# PiPico_Pinout.net
KiCad netlist of a schematic drawn in Altium Designer
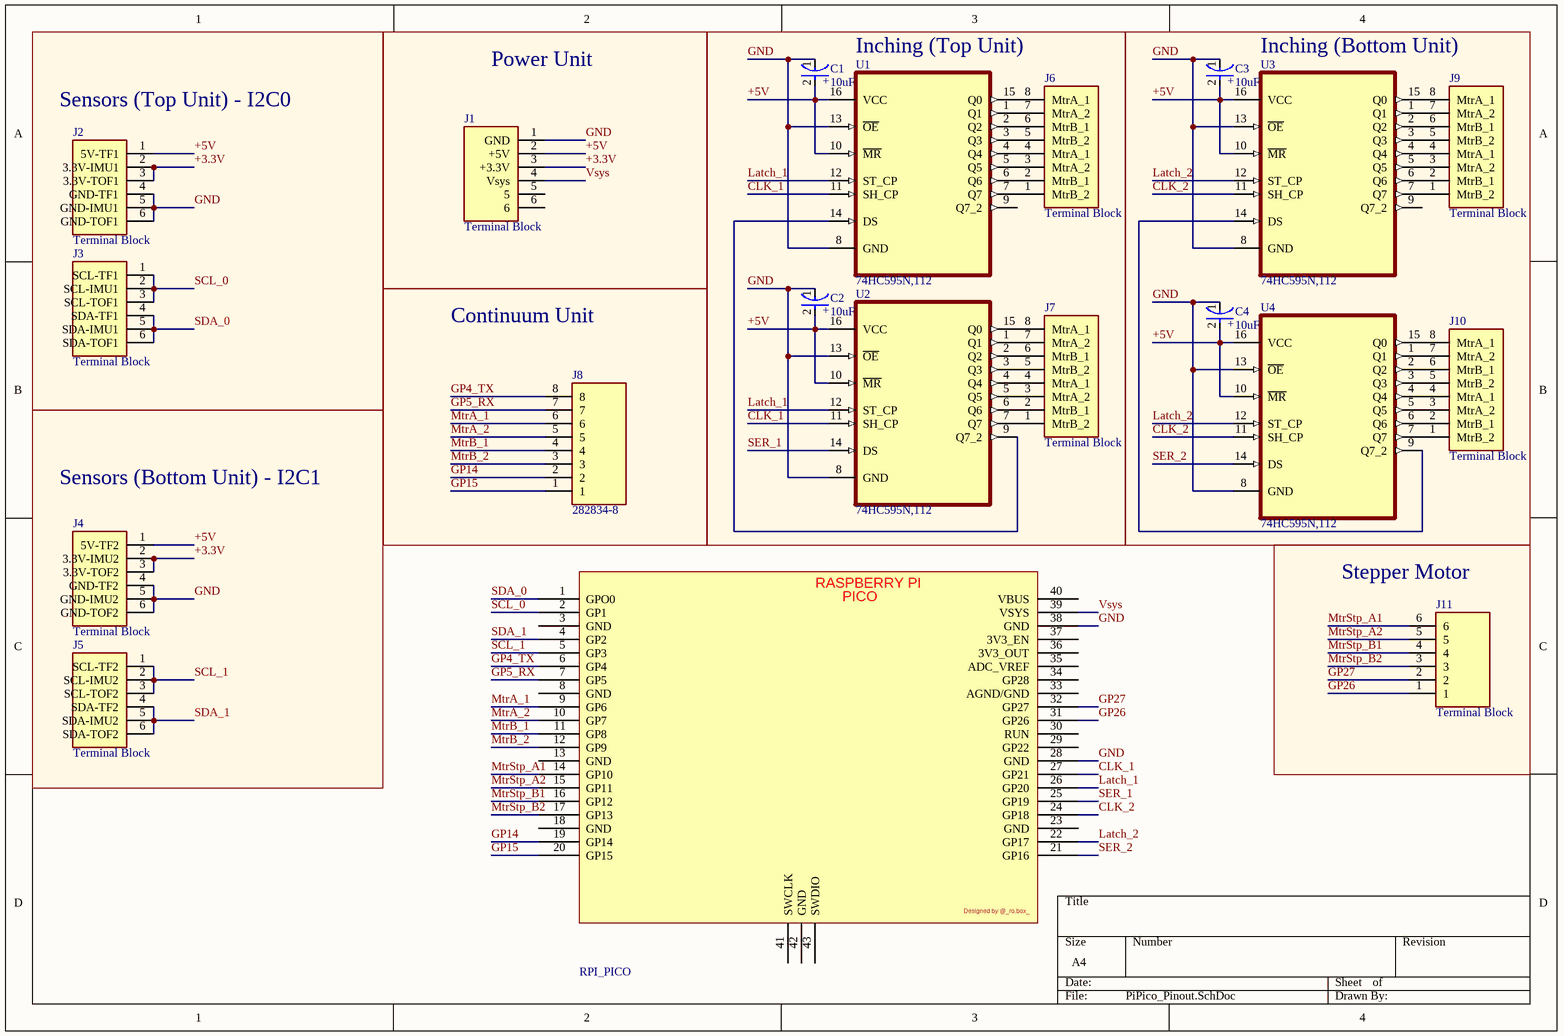
[diagram p0: PiPico_Pinout.SchDoc]

(export (version "E")
  (design (tool "Eeschema 10.0.6"))
  (components
    (comp (ref "C1")
      (value "10uF")
      (footprint "FP-TAP106K016SCS-MFG")
      (description "CAP TANT 10UF 10% 16V RADIAL")
      (fields (field (name "TOLERANCE") "10%") (field (name "VOLTAGE") "16V"))
      (libsource (lib "Altium Content Vault") (part "cf48714ba7e38822c1575c7ec0b6d1f"))
    )
    (comp (ref "C2")
      (value "10uF")
      (footprint "FP-TAP106K016SCS-MFG")
      (description "CAP TANT 10UF 10% 16V RADIAL")
      (fields (field (name "TOLERANCE") "10%") (field (name "VOLTAGE") "16V"))
      (libsource (lib "Altium Content Vault") (part "cf48714ba7e38822c1575c7ec0b6d1f"))
    )
    (comp (ref "C3")
      (value "10uF")
      (footprint "FP-TAP106K016SCS-MFG")
      (description "CAP TANT 10UF 10% 16V RADIAL")
      (fields (field (name "TOLERANCE") "10%") (field (name "VOLTAGE") "16V"))
      (libsource (lib "Altium Content Vault") (part "cf48714ba7e38822c1575c7ec0b6d1f"))
    )
    (comp (ref "C4")
      (value "10uF")
      (footprint "FP-TAP106K016SCS-MFG")
      (description "CAP TANT 10UF 10% 16V RADIAL")
      (fields (field (name "TOLERANCE") "10%") (field (name "VOLTAGE") "16V"))
      (libsource (lib "Altium Content Vault") (part "cf48714ba7e38822c1575c7ec0b6d1f"))
    )
    (comp (ref "J1")
      (value "Terminal Block")
      (footprint "TE_282834-6")
      (fields (field (name "MP") "282834-6") (field (name "MF") "{'manufacturer': 'TE Connectivity'}"))
      (libsource (lib "6pin_ScrewTerminal_2.54mm") (part "282834-6"))
    )
    (comp (ref "J2")
      (value "Terminal Block")
      (footprint "TE_282834-6")
      (fields (field (name "MP") "282834-6") (field (name "MF") "{'manufacturer': 'TE Connectivity'}"))
      (libsource (lib "6pin_ScrewTerminal_2.54mm") (part "282834-6"))
    )
    (comp (ref "J3")
      (value "Terminal Block")
      (footprint "TE_282834-6")
      (fields (field (name "MP") "282834-6") (field (name "MF") "{'manufacturer': 'TE Connectivity'}"))
      (libsource (lib "6pin_ScrewTerminal_2.54mm") (part "282834-6"))
    )
    (comp (ref "J4")
      (value "Terminal Block")
      (footprint "TE_282834-6")
      (fields (field (name "MP") "282834-6") (field (name "MF") "{'manufacturer': 'TE Connectivity'}"))
      (libsource (lib "6pin_ScrewTerminal_2.54mm") (part "282834-6"))
    )
    (comp (ref "J5")
      (value "Terminal Block")
      (footprint "TE_282834-6")
      (fields (field (name "MP") "282834-6") (field (name "MF") "{'manufacturer': 'TE Connectivity'}"))
      (libsource (lib "6pin_ScrewTerminal_2.54mm") (part "282834-6"))
    )
    (comp (ref "J6")
      (value "Terminal Block")
      (footprint "TE_282834-8")
      (description "Buchanan; Conn; Term Blk; PCB; 8; 2.54mm; Front; 30-16 AWG; Green; 10 A; 150 V")
      (fields (field (name "MF") "TE Connectivity") (field (name "DIGI-KEY_PART_NUMBER") "A98338-ND"))
      (libsource (lib "8pin_ScrewTerminal_2.54mm") (part "282834-8"))
    )
    (comp (ref "J7")
      (value "Terminal Block")
      (footprint "TE_282834-8")
      (description "Buchanan; Conn; Term Blk; PCB; 8; 2.54mm; Front; 30-16 AWG; Green; 10 A; 150 V")
      (fields (field (name "MF") "TE Connectivity") (field (name "DIGI-KEY_PART_NUMBER") "A98338-ND"))
      (libsource (lib "8pin_ScrewTerminal_2.54mm") (part "282834-8"))
    )
    (comp (ref "J8")
      (value "282834-8")
      (footprint "TE_282834-8")
      (description "Buchanan; Conn; Term Blk; PCB; 8; 2.54mm; Front; 30-16 AWG; Green; 10 A; 150 V")
      (fields (field (name "MF") "TE Connectivity") (field (name "DIGI-KEY_PART_NUMBER") "A98338-ND"))
      (libsource (lib "8pin_ScrewTerminal_2.54mm") (part "282834-8"))
    )
    (comp (ref "J9")
      (value "Terminal Block")
      (footprint "TE_282834-8")
      (description "Buchanan; Conn; Term Blk; PCB; 8; 2.54mm; Front; 30-16 AWG; Green; 10 A; 150 V")
      (fields (field (name "MF") "TE Connectivity") (field (name "DIGI-KEY_PART_NUMBER") "A98338-ND"))
      (libsource (lib "8pin_ScrewTerminal_2.54mm") (part "282834-8"))
    )
    (comp (ref "J10")
      (value "Terminal Block")
      (footprint "TE_282834-8")
      (description "Buchanan; Conn; Term Blk; PCB; 8; 2.54mm; Front; 30-16 AWG; Green; 10 A; 150 V")
      (fields (field (name "MF") "TE Connectivity") (field (name "DIGI-KEY_PART_NUMBER") "A98338-ND"))
      (libsource (lib "8pin_ScrewTerminal_2.54mm") (part "282834-8"))
    )
    (comp (ref "J11")
      (value "Terminal Block")
      (footprint "TE_282834-6")
      (fields (field (name "MP") "282834-6") (field (name "MF") "{'manufacturer': 'TE Connectivity'}"))
      (libsource (lib "") (part "282834-6_1"))
    )
    (comp (ref "RPI_PICO")
      (value "RPI_PICO")
      (footprint "RPI PICO 2020")
      (libsource (lib "RPI_PICO") (part "RPI_PICO"))
    )
    (comp (ref "U1")
      (value "74HC595N,112")
      (footprint "DIP254P762X420-16")
      (description "Shift Shift Register 1 Element 8 Bit 16-DIP")
      (fields (field (name "MF") "NXP USA"))
      (libsource (lib "74HC595N_112") (part "74HC595N,112"))
    )
    (comp (ref "U2")
      (value "74HC595N,112")
      (footprint "DIP254P762X420-16")
      (description "Shift Shift Register 1 Element 8 Bit 16-DIP")
      (fields (field (name "MF") "NXP USA"))
      (libsource (lib "74HC595N_112") (part "74HC595N,112"))
    )
    (comp (ref "U3")
      (value "74HC595N,112")
      (footprint "DIP254P762X420-16")
      (description "Shift Shift Register 1 Element 8 Bit 16-DIP")
      (fields (field (name "MF") "NXP USA"))
      (libsource (lib "74HC595N_112") (part "74HC595N,112"))
    )
    (comp (ref "U4")
      (value "74HC595N,112")
      (footprint "DIP254P762X420-16")
      (description "Shift Shift Register 1 Element 8 Bit 16-DIP")
      (fields (field (name "MF") "NXP USA"))
      (libsource (lib "74HC595N_112") (part "74HC595N,112"))
    )
  )
  (nets
    (net (code "1") (name "/+3.3V") (class "Default")
      (node (ref "J1") (pin "3") (pinfunction "SCL-TOF2_3") (pintype "passive"))
      (node (ref "J2") (pin "2") (pinfunction "SCL-IMU2_2") (pintype "passive"))
      (node (ref "J2") (pin "3") (pinfunction "SCL-TOF2_3") (pintype "passive"))
      (node (ref "J4") (pin "2") (pinfunction "SCL-IMU2_2") (pintype "passive"))
      (node (ref "J4") (pin "3") (pinfunction "SCL-TOF2_3") (pintype "passive"))
    )
    (net (code "2") (name "/+5V") (class "Default")
      (node (ref "C1") (pin "2") (pinfunction "A_2") (pintype "passive"))
      (node (ref "C2") (pin "2") (pinfunction "A_2") (pintype "passive"))
      (node (ref "C3") (pin "2") (pinfunction "A_2") (pintype "passive"))
      (node (ref "C4") (pin "2") (pinfunction "A_2") (pintype "passive"))
      (node (ref "J1") (pin "2") (pinfunction "SCL-IMU2_2") (pintype "passive"))
      (node (ref "J2") (pin "1") (pinfunction "SCL-TF2_1") (pintype "passive"))
      (node (ref "J4") (pin "1") (pinfunction "SCL-TF2_1") (pintype "passive"))
      (node (ref "U1") (pin "10") (pinfunction "~{MR}_10") (pintype "input"))
      (node (ref "U1") (pin "16") (pinfunction "VCC_16") (pintype "power_in"))
      (node (ref "U2") (pin "10") (pinfunction "~{MR}_10") (pintype "input"))
      (node (ref "U2") (pin "16") (pinfunction "VCC_16") (pintype "power_in"))
      (node (ref "U3") (pin "10") (pinfunction "~{MR}_10") (pintype "input"))
      (node (ref "U3") (pin "16") (pinfunction "VCC_16") (pintype "power_in"))
      (node (ref "U4") (pin "10") (pinfunction "~{MR}_10") (pintype "input"))
      (node (ref "U4") (pin "16") (pinfunction "VCC_16") (pintype "power_in"))
    )
    (net (code "3") (name "/CLK_1") (class "Default")
      (node (ref "RPI_PICO") (pin "27") (pinfunction "GP21_27") (pintype "passive"))
      (node (ref "U1") (pin "11") (pinfunction "SH_CP_11") (pintype "input"))
      (node (ref "U2") (pin "11") (pinfunction "SH_CP_11") (pintype "input"))
    )
    (net (code "4") (name "/CLK_2") (class "Default")
      (node (ref "RPI_PICO") (pin "24") (pinfunction "GP18_24") (pintype "passive"))
      (node (ref "U3") (pin "11") (pinfunction "SH_CP_11") (pintype "input"))
      (node (ref "U4") (pin "11") (pinfunction "SH_CP_11") (pintype "input"))
    )
    (net (code "5") (name "/GND") (class "Default")
      (node (ref "C1") (pin "1") (pinfunction "C_1") (pintype "passive"))
      (node (ref "C2") (pin "1") (pinfunction "C_1") (pintype "passive"))
      (node (ref "C3") (pin "1") (pinfunction "C_1") (pintype "passive"))
      (node (ref "C4") (pin "1") (pinfunction "C_1") (pintype "passive"))
      (node (ref "J1") (pin "1") (pinfunction "SCL-TF2_1") (pintype "passive"))
      (node (ref "J2") (pin "4") (pinfunction "SDA-TF2_4") (pintype "passive"))
      (node (ref "J2") (pin "5") (pinfunction "SDA-IMU2_5") (pintype "passive"))
      (node (ref "J2") (pin "6") (pinfunction "SDA-TOF2_6") (pintype "passive"))
      (node (ref "J4") (pin "4") (pinfunction "SDA-TF2_4") (pintype "passive"))
      (node (ref "J4") (pin "5") (pinfunction "SDA-IMU2_5") (pintype "passive"))
      (node (ref "J4") (pin "6") (pinfunction "SDA-TOF2_6") (pintype "passive"))
      (node (ref "RPI_PICO") (pin "28") (pinfunction "GND_28") (pintype "passive"))
      (node (ref "RPI_PICO") (pin "38") (pinfunction "GND_38") (pintype "passive"))
      (node (ref "U1") (pin "13") (pinfunction "~{OE}_13") (pintype "input"))
      (node (ref "U1") (pin "8") (pinfunction "GND_8") (pintype "passive"))
      (node (ref "U2") (pin "13") (pinfunction "~{OE}_13") (pintype "input"))
      (node (ref "U2") (pin "8") (pinfunction "GND_8") (pintype "passive"))
      (node (ref "U3") (pin "13") (pinfunction "~{OE}_13") (pintype "input"))
      (node (ref "U3") (pin "8") (pinfunction "GND_8") (pintype "passive"))
      (node (ref "U4") (pin "13") (pinfunction "~{OE}_13") (pintype "input"))
      (node (ref "U4") (pin "8") (pinfunction "GND_8") (pintype "passive"))
    )
    (net (code "6") (name "/GP4_TX") (class "Default")
      (node (ref "J8") (pin "8") (pinfunction "8_8") (pintype "passive"))
      (node (ref "RPI_PICO") (pin "6") (pinfunction "GP4_6") (pintype "passive"))
    )
    (net (code "7") (name "/GP5_RX") (class "Default")
      (node (ref "J8") (pin "7") (pinfunction "7_7") (pintype "passive"))
      (node (ref "RPI_PICO") (pin "7") (pinfunction "GP5_7") (pintype "passive"))
    )
    (net (code "8") (name "/GP14") (class "Default")
      (node (ref "J8") (pin "2") (pinfunction "2_2") (pintype "passive"))
      (node (ref "RPI_PICO") (pin "19") (pinfunction "GP14_19") (pintype "passive"))
    )
    (net (code "9") (name "/GP15") (class "Default")
      (node (ref "J8") (pin "1") (pinfunction "1_1") (pintype "passive"))
      (node (ref "RPI_PICO") (pin "20") (pinfunction "GP15_20") (pintype "passive"))
    )
    (net (code "10") (name "/GP26") (class "Default")
      (node (ref "J11") (pin "1") (pinfunction "1_1") (pintype "passive"))
      (node (ref "RPI_PICO") (pin "31") (pinfunction "GP26_31") (pintype "passive"))
    )
    (net (code "11") (name "/GP27") (class "Default")
      (node (ref "J11") (pin "2") (pinfunction "2_2") (pintype "passive"))
      (node (ref "RPI_PICO") (pin "32") (pinfunction "GP27_32") (pintype "passive"))
    )
    (net (code "12") (name "/Latch_1") (class "Default")
      (node (ref "RPI_PICO") (pin "26") (pinfunction "GP20_26") (pintype "passive"))
      (node (ref "U1") (pin "12") (pinfunction "ST_CP_12") (pintype "input"))
      (node (ref "U2") (pin "12") (pinfunction "ST_CP_12") (pintype "input"))
    )
    (net (code "13") (name "/Latch_2") (class "Default")
      (node (ref "RPI_PICO") (pin "22") (pinfunction "GP17_22") (pintype "passive"))
      (node (ref "U3") (pin "12") (pinfunction "ST_CP_12") (pintype "input"))
      (node (ref "U4") (pin "12") (pinfunction "ST_CP_12") (pintype "input"))
    )
    (net (code "14") (name "/MtrA_1") (class "Default")
      (node (ref "J8") (pin "6") (pinfunction "6_6") (pintype "passive"))
      (node (ref "RPI_PICO") (pin "9") (pinfunction "GP6_9") (pintype "passive"))
    )
    (net (code "15") (name "/MtrA_2") (class "Default")
      (node (ref "J8") (pin "5") (pinfunction "5_5") (pintype "passive"))
      (node (ref "RPI_PICO") (pin "10") (pinfunction "GP7_10") (pintype "passive"))
    )
    (net (code "16") (name "/MtrB_1") (class "Default")
      (node (ref "J8") (pin "4") (pinfunction "4_4") (pintype "passive"))
      (node (ref "RPI_PICO") (pin "11") (pinfunction "GP8_11") (pintype "passive"))
    )
    (net (code "17") (name "/MtrB_2") (class "Default")
      (node (ref "J8") (pin "3") (pinfunction "3_3") (pintype "passive"))
      (node (ref "RPI_PICO") (pin "12") (pinfunction "GP9_12") (pintype "passive"))
    )
    (net (code "18") (name "/MtrStp_A1") (class "Default")
      (node (ref "J11") (pin "6") (pinfunction "6_6") (pintype "passive"))
      (node (ref "RPI_PICO") (pin "14") (pinfunction "GP10_14") (pintype "passive"))
    )
    (net (code "19") (name "/MtrStp_A2") (class "Default")
      (node (ref "J11") (pin "5") (pinfunction "5_5") (pintype "passive"))
      (node (ref "RPI_PICO") (pin "15") (pinfunction "GP11_15") (pintype "passive"))
    )
    (net (code "20") (name "/MtrStp_B1") (class "Default")
      (node (ref "J11") (pin "4") (pinfunction "4_4") (pintype "passive"))
      (node (ref "RPI_PICO") (pin "16") (pinfunction "GP12_16") (pintype "passive"))
    )
    (net (code "21") (name "/MtrStp_B2") (class "Default")
      (node (ref "J11") (pin "3") (pinfunction "3_3") (pintype "passive"))
      (node (ref "RPI_PICO") (pin "17") (pinfunction "GP13_17") (pintype "passive"))
    )
    (net (code "22") (name "/SCL_0") (class "Default")
      (node (ref "J3") (pin "1") (pinfunction "SCL-TF2_1") (pintype "passive"))
      (node (ref "J3") (pin "2") (pinfunction "SCL-IMU2_2") (pintype "passive"))
      (node (ref "J3") (pin "3") (pinfunction "SCL-TOF2_3") (pintype "passive"))
      (node (ref "RPI_PICO") (pin "2") (pinfunction "GP1_2") (pintype "passive"))
    )
    (net (code "23") (name "/SCL_1") (class "Default")
      (node (ref "J5") (pin "1") (pinfunction "SCL-TF2_1") (pintype "passive"))
      (node (ref "J5") (pin "2") (pinfunction "SCL-IMU2_2") (pintype "passive"))
      (node (ref "J5") (pin "3") (pinfunction "SCL-TOF2_3") (pintype "passive"))
      (node (ref "RPI_PICO") (pin "5") (pinfunction "GP3_5") (pintype "passive"))
    )
    (net (code "24") (name "/SDA_0") (class "Default")
      (node (ref "J3") (pin "4") (pinfunction "SDA-TF2_4") (pintype "passive"))
      (node (ref "J3") (pin "5") (pinfunction "SDA-IMU2_5") (pintype "passive"))
      (node (ref "J3") (pin "6") (pinfunction "SDA-TOF2_6") (pintype "passive"))
      (node (ref "RPI_PICO") (pin "1") (pinfunction "GPO0_1") (pintype "passive"))
    )
    (net (code "25") (name "/SDA_1") (class "Default")
      (node (ref "J5") (pin "4") (pinfunction "SDA-TF2_4") (pintype "passive"))
      (node (ref "J5") (pin "5") (pinfunction "SDA-IMU2_5") (pintype "passive"))
      (node (ref "J5") (pin "6") (pinfunction "SDA-TOF2_6") (pintype "passive"))
      (node (ref "RPI_PICO") (pin "4") (pinfunction "GP2_4") (pintype "passive"))
    )
    (net (code "26") (name "/SER_1") (class "Default")
      (node (ref "RPI_PICO") (pin "25") (pinfunction "GP19_25") (pintype "passive"))
      (node (ref "U2") (pin "14") (pinfunction "DS_14") (pintype "input"))
    )
    (net (code "27") (name "/SER_2") (class "Default")
      (node (ref "RPI_PICO") (pin "21") (pinfunction "GP16_21") (pintype "passive"))
      (node (ref "U4") (pin "14") (pinfunction "DS_14") (pintype "input"))
    )
    (net (code "28") (name "/Vsys") (class "Default")
      (node (ref "J1") (pin "4") (pinfunction "SDA-TF2_4") (pintype "passive"))
      (node (ref "RPI_PICO") (pin "39") (pinfunction "VSYS_39") (pintype "passive"))
    )
    (net (code "29") (name "Net-(U1-DS)") (class "Default")
      (node (ref "U1") (pin "14") (pinfunction "DS_14") (pintype "input"))
      (node (ref "U2") (pin "9") (pinfunction "Q7_2_9") (pintype "output"))
    )
    (net (code "30") (name "Net-(U1-Q0)") (class "Default")
      (node (ref "J6") (pin "8") (pinfunction "8_8") (pintype "passive"))
      (node (ref "U1") (pin "15") (pinfunction "Q0_15") (pintype "output"))
    )
    (net (code "31") (name "Net-(U1-Q1)") (class "Default")
      (node (ref "J6") (pin "7") (pinfunction "7_7") (pintype "passive"))
      (node (ref "U1") (pin "1") (pinfunction "Q1_1") (pintype "output"))
    )
    (net (code "32") (name "Net-(U1-Q2)") (class "Default")
      (node (ref "J6") (pin "6") (pinfunction "6_6") (pintype "passive"))
      (node (ref "U1") (pin "2") (pinfunction "Q2_2") (pintype "output"))
    )
    (net (code "33") (name "Net-(U1-Q3)") (class "Default")
      (node (ref "J6") (pin "5") (pinfunction "5_5") (pintype "passive"))
      (node (ref "U1") (pin "3") (pinfunction "Q3_3") (pintype "output"))
    )
    (net (code "34") (name "Net-(U1-Q4)") (class "Default")
      (node (ref "J6") (pin "4") (pinfunction "4_4") (pintype "passive"))
      (node (ref "U1") (pin "4") (pinfunction "Q4_4") (pintype "output"))
    )
    (net (code "35") (name "Net-(U1-Q5)") (class "Default")
      (node (ref "J6") (pin "3") (pinfunction "3_3") (pintype "passive"))
      (node (ref "U1") (pin "5") (pinfunction "Q5_5") (pintype "output"))
    )
    (net (code "36") (name "Net-(U1-Q6)") (class "Default")
      (node (ref "J6") (pin "2") (pinfunction "2_2") (pintype "passive"))
      (node (ref "U1") (pin "6") (pinfunction "Q6_6") (pintype "output"))
    )
    (net (code "37") (name "Net-(U1-Q7)") (class "Default")
      (node (ref "J6") (pin "1") (pinfunction "1_1") (pintype "passive"))
      (node (ref "U1") (pin "7") (pinfunction "Q7_7") (pintype "output"))
    )
    (net (code "38") (name "Net-(U2-Q0)") (class "Default")
      (node (ref "J7") (pin "8") (pinfunction "8_8") (pintype "passive"))
      (node (ref "U2") (pin "15") (pinfunction "Q0_15") (pintype "output"))
    )
    (net (code "39") (name "Net-(U2-Q1)") (class "Default")
      (node (ref "J7") (pin "7") (pinfunction "7_7") (pintype "passive"))
      (node (ref "U2") (pin "1") (pinfunction "Q1_1") (pintype "output"))
    )
    (net (code "40") (name "Net-(U2-Q2)") (class "Default")
      (node (ref "J7") (pin "6") (pinfunction "6_6") (pintype "passive"))
      (node (ref "U2") (pin "2") (pinfunction "Q2_2") (pintype "output"))
    )
    (net (code "41") (name "Net-(U2-Q3)") (class "Default")
      (node (ref "J7") (pin "5") (pinfunction "5_5") (pintype "passive"))
      (node (ref "U2") (pin "3") (pinfunction "Q3_3") (pintype "output"))
    )
    (net (code "42") (name "Net-(U2-Q4)") (class "Default")
      (node (ref "J7") (pin "4") (pinfunction "4_4") (pintype "passive"))
      (node (ref "U2") (pin "4") (pinfunction "Q4_4") (pintype "output"))
    )
    (net (code "43") (name "Net-(U2-Q5)") (class "Default")
      (node (ref "J7") (pin "3") (pinfunction "3_3") (pintype "passive"))
      (node (ref "U2") (pin "5") (pinfunction "Q5_5") (pintype "output"))
    )
    (net (code "44") (name "Net-(U2-Q6)") (class "Default")
      (node (ref "J7") (pin "2") (pinfunction "2_2") (pintype "passive"))
      (node (ref "U2") (pin "6") (pinfunction "Q6_6") (pintype "output"))
    )
    (net (code "45") (name "Net-(U2-Q7)") (class "Default")
      (node (ref "J7") (pin "1") (pinfunction "1_1") (pintype "passive"))
      (node (ref "U2") (pin "7") (pinfunction "Q7_7") (pintype "output"))
    )
    (net (code "46") (name "Net-(U3-DS)") (class "Default")
      (node (ref "U3") (pin "14") (pinfunction "DS_14") (pintype "input"))
      (node (ref "U4") (pin "9") (pinfunction "Q7_2_9") (pintype "output"))
    )
    (net (code "47") (name "Net-(U3-Q0)") (class "Default")
      (node (ref "J9") (pin "8") (pinfunction "8_8") (pintype "passive"))
      (node (ref "U3") (pin "15") (pinfunction "Q0_15") (pintype "output"))
    )
    (net (code "48") (name "Net-(U3-Q1)") (class "Default")
      (node (ref "J9") (pin "7") (pinfunction "7_7") (pintype "passive"))
      (node (ref "U3") (pin "1") (pinfunction "Q1_1") (pintype "output"))
    )
    (net (code "49") (name "Net-(U3-Q2)") (class "Default")
      (node (ref "J9") (pin "6") (pinfunction "6_6") (pintype "passive"))
      (node (ref "U3") (pin "2") (pinfunction "Q2_2") (pintype "output"))
    )
    (net (code "50") (name "Net-(U3-Q3)") (class "Default")
      (node (ref "J9") (pin "5") (pinfunction "5_5") (pintype "passive"))
      (node (ref "U3") (pin "3") (pinfunction "Q3_3") (pintype "output"))
    )
    (net (code "51") (name "Net-(U3-Q4)") (class "Default")
      (node (ref "J9") (pin "4") (pinfunction "4_4") (pintype "passive"))
      (node (ref "U3") (pin "4") (pinfunction "Q4_4") (pintype "output"))
    )
    (net (code "52") (name "Net-(U3-Q5)") (class "Default")
      (node (ref "J9") (pin "3") (pinfunction "3_3") (pintype "passive"))
      (node (ref "U3") (pin "5") (pinfunction "Q5_5") (pintype "output"))
    )
    (net (code "53") (name "Net-(U3-Q6)") (class "Default")
      (node (ref "J9") (pin "2") (pinfunction "2_2") (pintype "passive"))
      (node (ref "U3") (pin "6") (pinfunction "Q6_6") (pintype "output"))
    )
    (net (code "54") (name "Net-(U3-Q7)") (class "Default")
      (node (ref "J9") (pin "1") (pinfunction "1_1") (pintype "passive"))
      (node (ref "U3") (pin "7") (pinfunction "Q7_7") (pintype "output"))
    )
    (net (code "55") (name "Net-(U4-Q0)") (class "Default")
      (node (ref "J10") (pin "8") (pinfunction "8_8") (pintype "passive"))
      (node (ref "U4") (pin "15") (pinfunction "Q0_15") (pintype "output"))
    )
    (net (code "56") (name "Net-(U4-Q1)") (class "Default")
      (node (ref "J10") (pin "7") (pinfunction "7_7") (pintype "passive"))
      (node (ref "U4") (pin "1") (pinfunction "Q1_1") (pintype "output"))
    )
    (net (code "57") (name "Net-(U4-Q2)") (class "Default")
      (node (ref "J10") (pin "6") (pinfunction "6_6") (pintype "passive"))
      (node (ref "U4") (pin "2") (pinfunction "Q2_2") (pintype "output"))
    )
    (net (code "58") (name "Net-(U4-Q3)") (class "Default")
      (node (ref "J10") (pin "5") (pinfunction "5_5") (pintype "passive"))
      (node (ref "U4") (pin "3") (pinfunction "Q3_3") (pintype "output"))
    )
    (net (code "59") (name "Net-(U4-Q4)") (class "Default")
      (node (ref "J10") (pin "4") (pinfunction "4_4") (pintype "passive"))
      (node (ref "U4") (pin "4") (pinfunction "Q4_4") (pintype "output"))
    )
    (net (code "60") (name "Net-(U4-Q5)") (class "Default")
      (node (ref "J10") (pin "3") (pinfunction "3_3") (pintype "passive"))
      (node (ref "U4") (pin "5") (pinfunction "Q5_5") (pintype "output"))
    )
    (net (code "61") (name "Net-(U4-Q6)") (class "Default")
      (node (ref "J10") (pin "2") (pinfunction "2_2") (pintype "passive"))
      (node (ref "U4") (pin "6") (pinfunction "Q6_6") (pintype "output"))
    )
    (net (code "62") (name "Net-(U4-Q7)") (class "Default")
      (node (ref "J10") (pin "1") (pinfunction "1_1") (pintype "passive"))
      (node (ref "U4") (pin "7") (pinfunction "Q7_7") (pintype "output"))
    )
    (net (code "63") (name "unconnected-(J1-SDA-IMU2-Pad5)") (class "Default")
      (node (ref "J1") (pin "5") (pinfunction "SDA-IMU2_5") (pintype "passive"))
    )
    (net (code "64") (name "unconnected-(J1-SDA-TOF2-Pad6)") (class "Default")
      (node (ref "J1") (pin "6") (pinfunction "SDA-TOF2_6") (pintype "passive"))
    )
    (net (code "65") (name "unconnected-(RPI_PICO-3V3_EN-Pad37)") (class "Default")
      (node (ref "RPI_PICO") (pin "37") (pinfunction "3V3_EN_37") (pintype "passive"))
    )
    (net (code "66") (name "unconnected-(RPI_PICO-3V3_OUT-Pad36)") (class "Default")
      (node (ref "RPI_PICO") (pin "36") (pinfunction "3V3_OUT_36") (pintype "passive"))
    )
    (net (code "67") (name "unconnected-(RPI_PICO-ADC_VREF-Pad35)") (class "Default")
      (node (ref "RPI_PICO") (pin "35") (pinfunction "ADC_VREF_35") (pintype "passive"))
    )
    (net (code "68") (name "unconnected-(RPI_PICO-AGND{slash}GND-Pad33)") (class "Default")
      (node (ref "RPI_PICO") (pin "33") (pinfunction "AGND/GND_33") (pintype "passive"))
    )
    (net (code "69") (name "unconnected-(RPI_PICO-GND-Pad3)") (class "Default")
      (node (ref "RPI_PICO") (pin "3") (pinfunction "GND_3") (pintype "passive"))
    )
    (net (code "70") (name "unconnected-(RPI_PICO-GND-Pad8)") (class "Default")
      (node (ref "RPI_PICO") (pin "8") (pinfunction "GND_8") (pintype "passive"))
    )
    (net (code "71") (name "unconnected-(RPI_PICO-GND-Pad13)") (class "Default")
      (node (ref "RPI_PICO") (pin "13") (pinfunction "GND_13") (pintype "passive"))
    )
    (net (code "72") (name "unconnected-(RPI_PICO-GND-Pad18)") (class "Default")
      (node (ref "RPI_PICO") (pin "18") (pinfunction "GND_18") (pintype "passive"))
    )
    (net (code "73") (name "unconnected-(RPI_PICO-GND-Pad23)") (class "Default")
      (node (ref "RPI_PICO") (pin "23") (pinfunction "GND_23") (pintype "passive"))
    )
    (net (code "74") (name "unconnected-(RPI_PICO-GND-Pad42)") (class "Default")
      (node (ref "RPI_PICO") (pin "42") (pinfunction "GND_42") (pintype "passive"))
    )
    (net (code "75") (name "unconnected-(RPI_PICO-GP22-Pad29)") (class "Default")
      (node (ref "RPI_PICO") (pin "29") (pinfunction "GP22_29") (pintype "passive"))
    )
    (net (code "76") (name "unconnected-(RPI_PICO-GP28-Pad34)") (class "Default")
      (node (ref "RPI_PICO") (pin "34") (pinfunction "GP28_34") (pintype "passive"))
    )
    (net (code "77") (name "unconnected-(RPI_PICO-RUN-Pad30)") (class "Default")
      (node (ref "RPI_PICO") (pin "30") (pinfunction "RUN_30") (pintype "passive"))
    )
    (net (code "78") (name "unconnected-(RPI_PICO-SWCLK-Pad41)") (class "Default")
      (node (ref "RPI_PICO") (pin "41") (pinfunction "SWCLK_41") (pintype "passive"))
    )
    (net (code "79") (name "unconnected-(RPI_PICO-SWDIO-Pad43)") (class "Default")
      (node (ref "RPI_PICO") (pin "43") (pinfunction "SWDIO_43") (pintype "passive"))
    )
    (net (code "80") (name "unconnected-(RPI_PICO-VBUS-Pad40)") (class "Default")
      (node (ref "RPI_PICO") (pin "40") (pinfunction "VBUS_40") (pintype "passive"))
    )
    (net (code "81") (name "unconnected-(U1-Q7_2-Pad9)") (class "Default")
      (node (ref "U1") (pin "9") (pinfunction "Q7_2_9") (pintype "output"))
    )
    (net (code "82") (name "unconnected-(U3-Q7_2-Pad9)") (class "Default")
      (node (ref "U3") (pin "9") (pinfunction "Q7_2_9") (pintype "output"))
    )
  )
)
